# InkTime_SCH.net
KiCad netlist of a schematic drawn in EAGLE
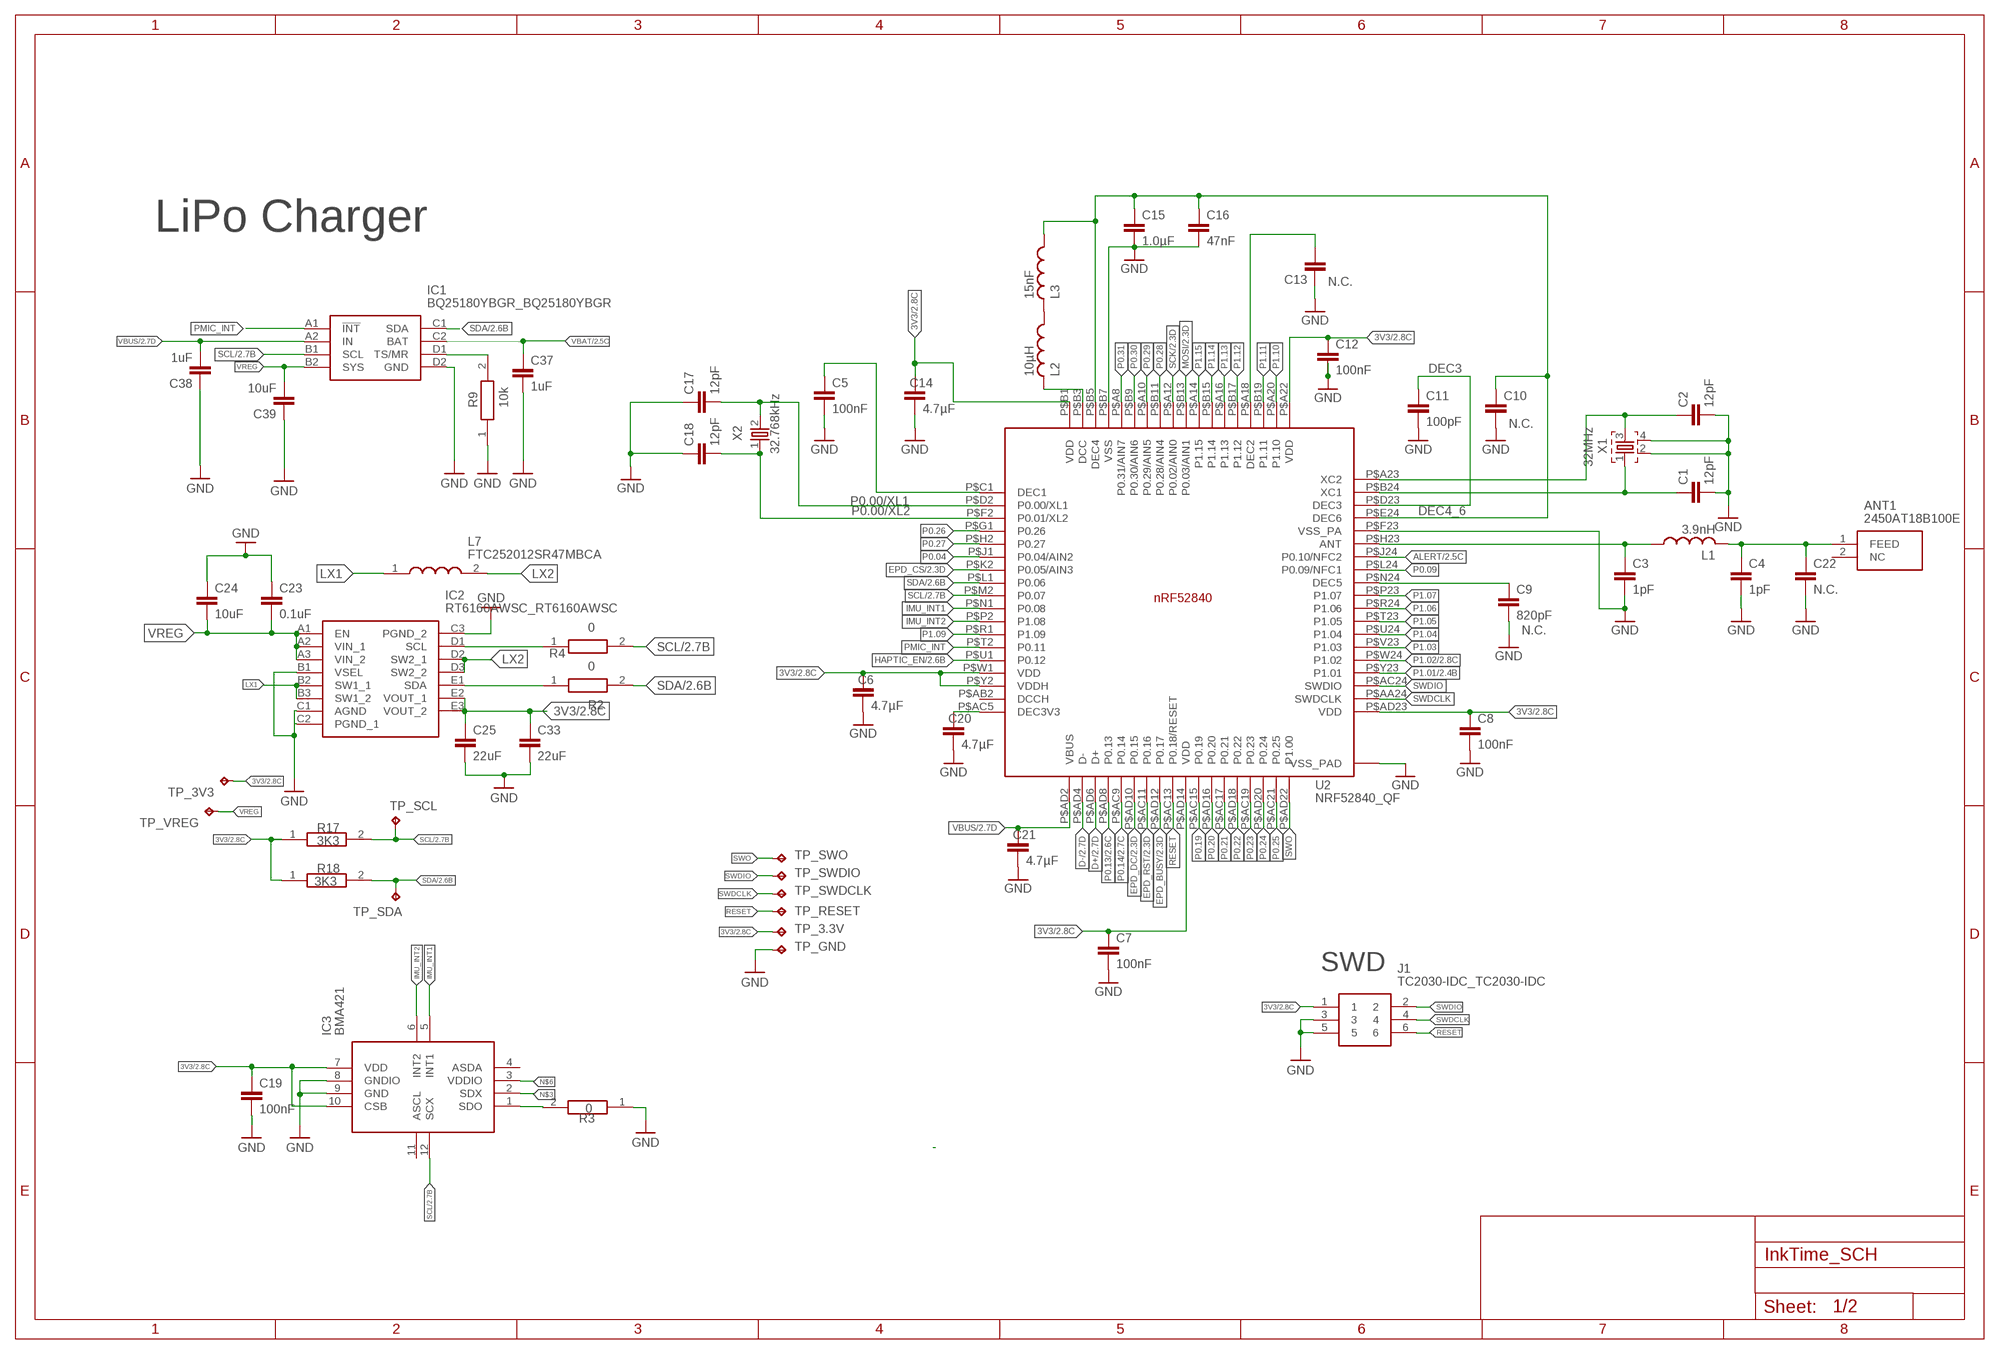
[diagram p0: schematic, sheet 1]
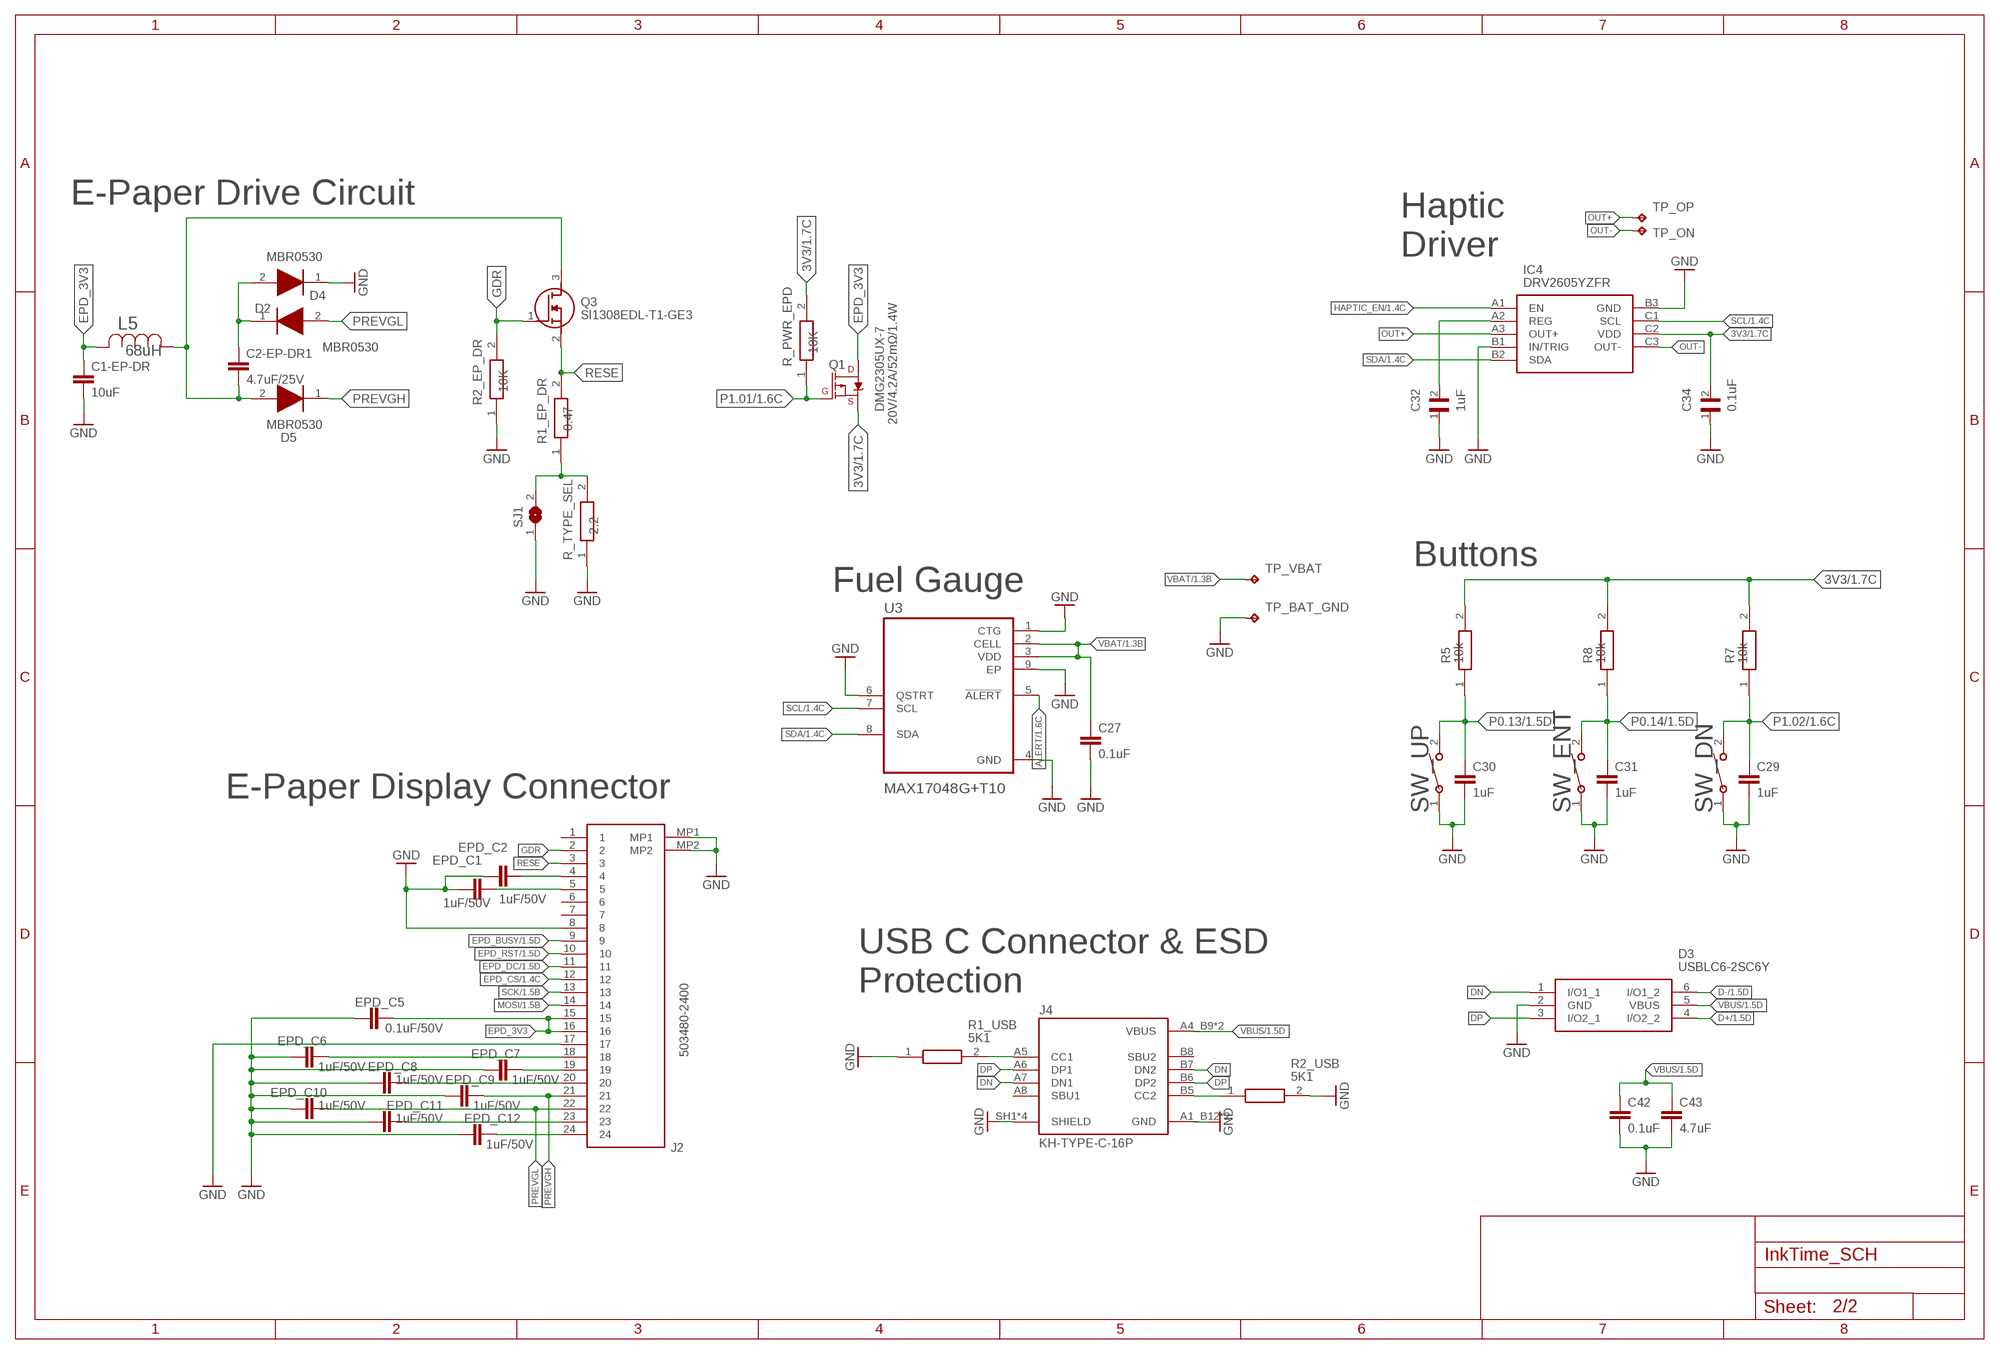
[diagram p1: schematic, sheet 2]

(export (version "E")
  (design (tool "Eeschema 10.0.6"))
  (components
    (comp (ref "ANT1")
      (value "2450AT18B100E")
      (footprint "eagle-import:2450AT18B100E_ANTC3216X140N")
      (fields (field (name "MOUSER_PART_NUMBER") "609-2450AT18B100E"))
      (libsource (lib "eagle-import") (part "2450AT18B100E_2450AT18B100E"))
    )
    (comp (ref "C1")
      (value "12pF")
      (footprint "eagle-import:NORDIC_NRF_3_RESC0201_L")
      (libsource (lib "eagle-import") (part "NORDIC_NRF_3_CAPACITOR_0201_L"))
    )
    (comp (ref "C2")
      (value "12pF")
      (footprint "eagle-import:NORDIC_NRF_3_RESC0201_L")
      (libsource (lib "eagle-import") (part "NORDIC_NRF_3_CAPACITOR_0201_L"))
    )
    (comp (ref "C3")
      (value "1pF")
      (footprint "eagle-import:NORDIC_NRF_3_RESC0201_L")
      (libsource (lib "eagle-import") (part "NORDIC_NRF_3_CAPACITOR_0201_L"))
    )
    (comp (ref "C4")
      (value "1pF")
      (footprint "eagle-import:NORDIC_NRF_3_RESC0201_L")
      (libsource (lib "eagle-import") (part "NORDIC_NRF_3_CAPACITOR_0201_L"))
    )
    (comp (ref "C5")
      (value "100nF")
      (footprint "eagle-import:NORDIC_NRF_3_RESC0201_L")
      (libsource (lib "eagle-import") (part "NORDIC_NRF_3_CAPACITOR_0201_L"))
    )
    (comp (ref "C6")
      (value "4.7µF")
      (footprint "eagle-import:NORDIC_NRF_3_RESC0402_L")
      (libsource (lib "eagle-import") (part "NORDIC_NRF_3_CAPACITOR_0402_L"))
    )
    (comp (ref "C7")
      (value "100nF")
      (footprint "eagle-import:NORDIC_NRF_3_RESC0201_L")
      (libsource (lib "eagle-import") (part "NORDIC_NRF_3_CAPACITOR_0201_L"))
    )
    (comp (ref "C8")
      (value "100nF")
      (footprint "eagle-import:NORDIC_NRF_3_RESC0201_L")
      (libsource (lib "eagle-import") (part "NORDIC_NRF_3_CAPACITOR_0201_L"))
    )
    (comp (ref "C9")
      (value "820pF")
      (footprint "eagle-import:NORDIC_NRF_3_RESC0201_L")
      (libsource (lib "eagle-import") (part "NORDIC_NRF_3_CAPACITOR_0201_L"))
    )
    (comp (ref "C10")
      (value "NORDIC_NRF_3_CAPACITOR_0201_L")
      (footprint "eagle-import:NORDIC_NRF_3_RESC0201_L")
      (libsource (lib "eagle-import") (part "NORDIC_NRF_3_CAPACITOR_0201_L"))
    )
    (comp (ref "C11")
      (value "100pF")
      (footprint "eagle-import:NORDIC_NRF_3_RESC0201_L")
      (libsource (lib "eagle-import") (part "NORDIC_NRF_3_CAPACITOR_0201_L"))
    )
    (comp (ref "C12")
      (value "100nF")
      (footprint "eagle-import:NORDIC_NRF_3_RESC0201_L")
      (libsource (lib "eagle-import") (part "NORDIC_NRF_3_CAPACITOR_0201_L"))
    )
    (comp (ref "C13")
      (value "NORDIC_NRF_3_CAPACITOR_0201_L")
      (footprint "eagle-import:NORDIC_NRF_3_RESC0201_L")
      (libsource (lib "eagle-import") (part "NORDIC_NRF_3_CAPACITOR_0201_L"))
    )
    (comp (ref "C14")
      (value "4.7µF")
      (footprint "eagle-import:NORDIC_NRF_3_RESC0402_L")
      (libsource (lib "eagle-import") (part "NORDIC_NRF_3_CAPACITOR_0402_L"))
    )
    (comp (ref "C15")
      (value "1.0µF")
      (footprint "eagle-import:NORDIC_NRF_3_RESC0402_L")
      (libsource (lib "eagle-import") (part "NORDIC_NRF_3_CAPACITOR_0402_L"))
    )
    (comp (ref "C16")
      (value "47nF")
      (footprint "eagle-import:NORDIC_NRF_3_RESC0201_L")
      (libsource (lib "eagle-import") (part "NORDIC_NRF_3_CAPACITOR_0201_L"))
    )
    (comp (ref "C17")
      (value "12pF")
      (footprint "eagle-import:NORDIC_NRF_3_RESC0201_L")
      (libsource (lib "eagle-import") (part "NORDIC_NRF_3_CAPACITOR_0201_L"))
    )
    (comp (ref "C18")
      (value "12pF")
      (footprint "eagle-import:NORDIC_NRF_3_RESC0201_L")
      (libsource (lib "eagle-import") (part "NORDIC_NRF_3_CAPACITOR_0201_L"))
    )
    (comp (ref "C19")
      (value "100nF")
      (footprint "eagle-import:NORDIC_NRF_3_RESC0201_L")
      (libsource (lib "eagle-import") (part "InkTime_v5_vf.cpZt_fPRRlWDsZKqzDdmXA_NORDIC_NRF_3_CAPACITOR_0201_L"))
    )
    (comp (ref "C20")
      (value "4.7µF")
      (footprint "eagle-import:NORDIC_NRF_3_RESC0402_L")
      (libsource (lib "eagle-import") (part "NORDIC_NRF_3_CAPACITOR_0402_L"))
    )
    (comp (ref "C21")
      (value "4.7µF")
      (footprint "eagle-import:NORDIC_NRF_3_RESC0402_L")
      (libsource (lib "eagle-import") (part "NORDIC_NRF_3_CAPACITOR_0402_L"))
    )
    (comp (ref "C22")
      (value "N.C.")
      (footprint "eagle-import:NORDIC_NRF_3_RESC0201_L")
      (libsource (lib "eagle-import") (part "NORDIC_NRF_3_CAPACITOR_0201_L"))
    )
    (comp (ref "C23")
      (value "0.1uF")
      (footprint "eagle-import:NORDIC_NRF_3_RESC0201_L")
      (libsource (lib "eagle-import") (part "InkTime_v5_vf.cpZt_fPRRlWDsZKqzDdmXA_NORDIC_NRF_3_CAPACITOR_0201_L"))
    )
    (comp (ref "C24")
      (value "10uF")
      (footprint "eagle-import:NORDIC_NRF_3_RESC0402_L")
      (libsource (lib "eagle-import") (part "InkTime_v5_vf.cpZt_fPRRlWDsZKqzDdmXA_NORDIC_NRF_3_CAPACITOR_0402_L"))
    )
    (comp (ref "C25")
      (value "22uF")
      (footprint "eagle-import:NORDIC_NRF_3_RESC0402_L")
      (libsource (lib "eagle-import") (part "InkTime_v5_vf.cpZt_fPRRlWDsZKqzDdmXA_NORDIC_NRF_3_CAPACITOR_0402_L"))
    )
    (comp (ref "C33")
      (value "22uF")
      (footprint "eagle-import:NORDIC_NRF_3_RESC0402_L")
      (libsource (lib "eagle-import") (part "InkTime_v5_vf.cpZt_fPRRlWDsZKqzDdmXA_NORDIC_NRF_3_CAPACITOR_0402_L"))
    )
    (comp (ref "C37")
      (value "1uF")
      (footprint "eagle-import:NORDIC_NRF_3_RESC0402_L")
      (libsource (lib "eagle-import") (part "InkTime_v5_vf.cpZt_fPRRlWDsZKqzDdmXA_NORDIC_NRF_3_CAPACITOR_0402_L"))
    )
    (comp (ref "C38")
      (value "1uF")
      (footprint "eagle-import:NORDIC_NRF_3_RESC0402_L")
      (libsource (lib "eagle-import") (part "InkTime_v5_vf.cpZt_fPRRlWDsZKqzDdmXA_NORDIC_NRF_3_CAPACITOR_0402_L"))
    )
    (comp (ref "C39")
      (value "10uF")
      (footprint "eagle-import:NORDIC_NRF_3_RESC0402_L")
      (libsource (lib "eagle-import") (part "InkTime_v5_vf.cpZt_fPRRlWDsZKqzDdmXA_NORDIC_NRF_3_CAPACITOR_0402_L"))
    )
    (comp (ref "IC1")
      (value "BQ25180YBGR_BQ25180YBGR")
      (footprint "eagle-import:BQ25180YBGR_BGA8C40P2X4_100X155X50")
      (fields
        (field (name "ARROW_PART_NUMBER") "BQ25180YBGR")
        (field (name "MOUSER_PART_NUMBER") "595-BQ25180YBGR")
      )
      (libsource (lib "eagle-import") (part "BQ25180YBGR_BQ25180YBGR"))
    )
    (comp (ref "IC2")
      (value "RT6160AWSC_RT6160AWSC")
      (footprint "eagle-import:RT6160AWSC_BGA15C40P3X5_140X230X60")
      (fields
        (field (name "MANUFACTURER_PART_NUMBER") "RT6160AWSC")
        (field (name "MOUSER_PART_NUMBER") "835-RT6160AWSC")
      )
      (libsource (lib "eagle-import") (part "RT6160AWSC_RT6160AWSC"))
    )
    (comp (ref "IC3")
      (value "BMA421")
      (footprint "eagle-import:BMA423_BMA423")
      (fields (field (name "ARROW_PART_NUMBER") "BMA423") (field (name "MOUSER_PART_NUMBER") "262-BMA423"))
      (libsource (lib "eagle-import") (part "BMA423_BMA423"))
    )
    (comp (ref "J1")
      (value "TC2030-IDC_TC2030-IDC")
      (footprint "eagle-import:TC2030-IDC_TC2030IDC")
      (fields (field (name "MANUFACTURER_PART_NUMBER") "TC2030-IDC"))
      (libsource (lib "eagle-import") (part "TC2030-IDC_TC2030-IDC"))
    )
    (comp (ref "L1")
      (value "3.9nH")
      (footprint "eagle-import:NORDIC_NRF_2_RESC0402_L")
      (libsource (lib "eagle-import") (part "NORDIC_NRF_2_INDUCTOR_0402_L"))
    )
    (comp (ref "L2")
      (value "10µH")
      (footprint "eagle-import:NORDIC_NRF_2_RESC0402_L")
      (libsource (lib "eagle-import") (part "NORDIC_NRF_2_INDUCTOR_0402_L"))
    )
    (comp (ref "L3")
      (value "15nF")
      (footprint "eagle-import:NORDIC_NRF_2_RESC0402_L")
      (libsource (lib "eagle-import") (part "NORDIC_NRF_2_INDUCTOR_0402_L"))
    )
    (comp (ref "L7")
      (value "FTC252012SR47MBCA")
      (footprint "eagle-import:MLP2016SR47MT0S1_INDC2016X100N")
      (libsource (lib "eagle-import") (part "MLP2016SR47MT0S1_FTC252012SR47MBCA"))
    )
    (comp (ref "R2")
      (value "0")
      (footprint "eagle-import:ERA-1AEB3401C_0201")
      (libsource (lib "eagle-import") (part "ERA-1AEB3401C_CPF0201D7K68C1"))
    )
    (comp (ref "R3")
      (value "0")
      (footprint "eagle-import:ERA-1AEB3401C_0201")
      (libsource (lib "eagle-import") (part "ERA-1AEB3401C_CPF0201D7K68C1"))
    )
    (comp (ref "R4")
      (value "0")
      (footprint "eagle-import:ERA-1AEB3401C_0201")
      (libsource (lib "eagle-import") (part "ERA-1AEB3401C_CPF0201D7K68C1"))
    )
    (comp (ref "R9")
      (value "10k")
      (footprint "eagle-import:ERA-1AEB3401C_0201")
      (libsource (lib "eagle-import") (part "ERA-1AEB3401C_CPF0201D7K68C1"))
    )
    (comp (ref "R17")
      (value "3K3")
      (footprint "eagle-import:ERA-1AEB3401C_0201")
      (libsource (lib "eagle-import") (part "ERA-1AEB3401C_CPF0201D7K68C1"))
    )
    (comp (ref "R18")
      (value "3K3")
      (footprint "eagle-import:ERA-1AEB3401C_0201")
      (libsource (lib "eagle-import") (part "ERA-1AEB3401C_CPF0201D7K68C1"))
    )
    (comp (ref "TP_3.3V")
      (value "HECTOR_WATCH_1_TPTP20R")
      (footprint "eagle-import:HECTOR_WATCH_1_TP20R")
      (libsource (lib "eagle-import") (part "InkTime_v5_vf.cpZt_fPRRlWDsZKqzDdmXA_HECTOR_WATCH_1_TPTP20R"))
    )
    (comp (ref "TP_3V3")
      (value "HECTOR_WATCH_1_TPTP20R")
      (footprint "eagle-import:HECTOR_WATCH_1_TP20R")
      (libsource (lib "eagle-import") (part "InkTime_v5_vf.cpZt_fPRRlWDsZKqzDdmXA_HECTOR_WATCH_1_TPTP20R"))
    )
    (comp (ref "TP_GND")
      (value "HECTOR_WATCH_1_TPTP20R")
      (footprint "eagle-import:HECTOR_WATCH_1_TP20R")
      (libsource (lib "eagle-import") (part "InkTime_v5_vf.cpZt_fPRRlWDsZKqzDdmXA_HECTOR_WATCH_1_TPTP20R"))
    )
    (comp (ref "TP_RESET")
      (value "HECTOR_WATCH_1_TPTP20R")
      (footprint "eagle-import:HECTOR_WATCH_1_TP20R")
      (libsource (lib "eagle-import") (part "InkTime_v5_vf.cpZt_fPRRlWDsZKqzDdmXA_HECTOR_WATCH_1_TPTP20R"))
    )
    (comp (ref "TP_SCL")
      (value "HECTOR_WATCH_1_TPTP20R")
      (footprint "eagle-import:HECTOR_WATCH_1_TP20R")
      (libsource (lib "eagle-import") (part "InkTime_v5_vf.cpZt_fPRRlWDsZKqzDdmXA_HECTOR_WATCH_1_TPTP20R"))
    )
    (comp (ref "TP_SDA")
      (value "HECTOR_WATCH_1_TPTP20R")
      (footprint "eagle-import:HECTOR_WATCH_1_TP20R")
      (libsource (lib "eagle-import") (part "InkTime_v5_vf.cpZt_fPRRlWDsZKqzDdmXA_HECTOR_WATCH_1_TPTP20R"))
    )
    (comp (ref "TP_SWDCLK")
      (value "HECTOR_WATCH_1_TPTP20R")
      (footprint "eagle-import:HECTOR_WATCH_1_TP20R")
      (libsource (lib "eagle-import") (part "InkTime_v5_vf.cpZt_fPRRlWDsZKqzDdmXA_HECTOR_WATCH_1_TPTP20R"))
    )
    (comp (ref "TP_SWDIO")
      (value "HECTOR_WATCH_1_TPTP20R")
      (footprint "eagle-import:HECTOR_WATCH_1_TP20R")
      (libsource (lib "eagle-import") (part "InkTime_v5_vf.cpZt_fPRRlWDsZKqzDdmXA_HECTOR_WATCH_1_TPTP20R"))
    )
    (comp (ref "TP_SWO")
      (value "HECTOR_WATCH_1_TPTP20R")
      (footprint "eagle-import:HECTOR_WATCH_1_TP20R")
      (libsource (lib "eagle-import") (part "InkTime_v5_vf.cpZt_fPRRlWDsZKqzDdmXA_HECTOR_WATCH_1_TPTP20R"))
    )
    (comp (ref "TP_VREG")
      (value "HECTOR_WATCH_1_TPTP20R")
      (footprint "eagle-import:HECTOR_WATCH_1_TP20R")
      (libsource (lib "eagle-import") (part "InkTime_v5_vf.cpZt_fPRRlWDsZKqzDdmXA_HECTOR_WATCH_1_TPTP20R"))
    )
    (comp (ref "U2")
      (value "NRF52840_QF")
      (footprint "eagle-import:NORDIC_NRF_4_AQFN50P700X700X85_HS-74N")
      (libsource (lib "eagle-import") (part "NORDIC_NRF_4_NRF52840_QF"))
    )
    (comp (ref "X1")
      (value "32MHz")
      (footprint "eagle-import:NORDIC_NRF_BT-XTAL_2016_N")
      (libsource (lib "eagle-import") (part "NORDIC_NRF_XTAL_32MHZ"))
    )
    (comp (ref "X2")
      (value "32.768kHz")
      (footprint "eagle-import:NORDIC_NRF_1_XTAL_3215_N")
      (libsource (lib "eagle-import") (part "NORDIC_NRF_1_XTAL_32KHZ"))
    )
    (comp (ref "C1-EP-DR")
      (value "10uF")
      (footprint "eagle-import:NORDIC_NRF_3_RESC0402_L")
      (libsource (lib "eagle-import") (part "NORDIC_NRF_3_CAPACITOR_0402_L"))
    )
    (comp (ref "C2-EP-DR1")
      (value "4.7uF/25V")
      (footprint "eagle-import:NORDIC_NRF_3_RESC0402_L")
      (libsource (lib "eagle-import") (part "NORDIC_NRF_3_CAPACITOR_0402_L"))
    )
    (comp (ref "C27")
      (value "0.1uF")
      (footprint "eagle-import:NORDIC_NRF_3_RESC0201_L")
      (libsource (lib "eagle-import") (part "NORDIC_NRF_3_CAPACITOR_0201_L"))
    )
    (comp (ref "C29")
      (value "1uF")
      (footprint "eagle-import:NORDIC_NRF_3_RESC0402_L")
      (libsource (lib "eagle-import") (part "NORDIC_NRF_3_CAPACITOR_0402_L"))
    )
    (comp (ref "C30")
      (value "1uF")
      (footprint "eagle-import:NORDIC_NRF_3_RESC0402_L")
      (libsource (lib "eagle-import") (part "NORDIC_NRF_3_CAPACITOR_0402_L"))
    )
    (comp (ref "C31")
      (value "1uF")
      (footprint "eagle-import:NORDIC_NRF_3_RESC0402_L")
      (libsource (lib "eagle-import") (part "NORDIC_NRF_3_CAPACITOR_0402_L"))
    )
    (comp (ref "C32")
      (value "1uF")
      (footprint "eagle-import:GRM011R60J152KE01L_2_CAPC0201X13N")
      (fields (field (name "MF") "Murata") (field (name "MP") "GRM011R60J152KE01L"))
      (libsource (lib "eagle-import") (part "GRM011R60J152KE01L_2_GRM011R60J152KE01L"))
    )
    (comp (ref "C34")
      (value "0.1uF")
      (footprint "eagle-import:GRM011R60J152KE01L_2_CAPC0201X13N")
      (fields (field (name "MF") "Murata") (field (name "MP") "GRM011R60J152KE01L"))
      (libsource (lib "eagle-import") (part "GRM011R60J152KE01L_2_GRM011R60J152KE01L"))
    )
    (comp (ref "C42")
      (value "0.1uF")
      (footprint "eagle-import:NORDIC_NRF_3_RESC0201_L")
      (libsource (lib "eagle-import") (part "NORDIC_NRF_3_CAPACITOR_0201_L"))
    )
    (comp (ref "C43")
      (value "4.7uF")
      (footprint "eagle-import:NORDIC_NRF_3_RESC0402_L")
      (libsource (lib "eagle-import") (part "NORDIC_NRF_3_CAPACITOR_0402_L"))
    )
    (comp (ref "D2")
      (value "MBR0530")
      (footprint "eagle-import:ESP32_C6_LIBRARY_5_SOD3716X135N")
      (fields (field (name "MF") "ON Semiconductor"))
      (libsource (lib "eagle-import") (part "ESP32_C6_LIBRARY_5_MBR0530"))
    )
    (comp (ref "D3")
      (value "USBLC6-2SC6Y")
      (footprint "eagle-import:ESP32_C6_LIBRARY_3_SOT95P280X145-6N")
      (fields (field (name "MF") "STMicroelectronics"))
      (libsource (lib "eagle-import") (part "ESP32_C6_LIBRARY_3_USBLC6-2SC6Y"))
    )
    (comp (ref "D4")
      (value "MBR0530")
      (footprint "eagle-import:ESP32_C6_LIBRARY_5_SOD3716X135N")
      (fields (field (name "MF") "ON Semiconductor"))
      (libsource (lib "eagle-import") (part "ESP32_C6_LIBRARY_5_MBR0530"))
    )
    (comp (ref "D5")
      (value "MBR0530")
      (footprint "eagle-import:ESP32_C6_LIBRARY_5_SOD3716X135N")
      (fields (field (name "MF") "ON Semiconductor"))
      (libsource (lib "eagle-import") (part "ESP32_C6_LIBRARY_5_MBR0530"))
    )
    (comp (ref "EPD_C1")
      (value "1uF/50V")
      (footprint "eagle-import:NORDIC_NRF_3_RESC0402_L")
      (libsource (lib "eagle-import") (part "NORDIC_NRF_3_CAPACITOR_0402_L"))
    )
    (comp (ref "EPD_C2")
      (value "1uF/50V")
      (footprint "eagle-import:NORDIC_NRF_3_RESC0402_L")
      (libsource (lib "eagle-import") (part "NORDIC_NRF_3_CAPACITOR_0402_L"))
    )
    (comp (ref "EPD_C5")
      (value "0.1uF/50V")
      (footprint "eagle-import:NORDIC_NRF_3_RESC0201_L")
      (libsource (lib "eagle-import") (part "NORDIC_NRF_3_CAPACITOR_0201_L"))
    )
    (comp (ref "EPD_C6")
      (value "1uF/50V")
      (footprint "eagle-import:NORDIC_NRF_3_RESC0402_L")
      (libsource (lib "eagle-import") (part "NORDIC_NRF_3_CAPACITOR_0402_L"))
    )
    (comp (ref "EPD_C7")
      (value "1uF/50V")
      (footprint "eagle-import:NORDIC_NRF_3_RESC0402_L")
      (libsource (lib "eagle-import") (part "NORDIC_NRF_3_CAPACITOR_0402_L"))
    )
    (comp (ref "EPD_C8")
      (value "1uF/50V")
      (footprint "eagle-import:NORDIC_NRF_3_RESC0402_L")
      (libsource (lib "eagle-import") (part "NORDIC_NRF_3_CAPACITOR_0402_L"))
    )
    (comp (ref "EPD_C9")
      (value "1uF/50V")
      (footprint "eagle-import:NORDIC_NRF_3_RESC0402_L")
      (libsource (lib "eagle-import") (part "NORDIC_NRF_3_CAPACITOR_0402_L"))
    )
    (comp (ref "EPD_C10")
      (value "1uF/50V")
      (footprint "eagle-import:NORDIC_NRF_3_RESC0402_L")
      (libsource (lib "eagle-import") (part "NORDIC_NRF_3_CAPACITOR_0402_L"))
    )
    (comp (ref "EPD_C11")
      (value "1uF/50V")
      (footprint "eagle-import:NORDIC_NRF_3_RESC0402_L")
      (libsource (lib "eagle-import") (part "NORDIC_NRF_3_CAPACITOR_0402_L"))
    )
    (comp (ref "EPD_C12")
      (value "1uF/50V")
      (footprint "eagle-import:NORDIC_NRF_3_RESC0402_L")
      (libsource (lib "eagle-import") (part "NORDIC_NRF_3_CAPACITOR_0402_L"))
    )
    (comp (ref "IC4")
      (value "DRV2605YZFR")
      (footprint "eagle-import:DRV2605YZFR_BGA9C50P3X3_144X144X62")
      (libsource (lib "eagle-import") (part "DRV2605YZFR_DRV2605YZFR"))
    )
    (comp (ref "J2")
      (value "503480-2400")
      (footprint "eagle-import:503480-2400_5034802400")
      (fields (field (name "MOUSER_PART_NUMBER") "538-503480-2400"))
      (libsource (lib "eagle-import") (part "503480-2400_503480-2400"))
    )
    (comp (ref "J4")
      (value "KH-TYPE-C-16P")
      (footprint "eagle-import:KH-TYPE-C-16P_KINGHELM_KH-TYPE-C-16P")
      (fields (field (name "MF") "kinghelm"))
      (libsource (lib "eagle-import") (part "KH-TYPE-C-16P_KH-TYPE-C-16P"))
    )
    (comp (ref "L5")
      (value "68uH")
      (footprint "eagle-import:ESP32_C6_LIBRARY_2_IND_4828-WE-TPC_WRE")
      (fields
        (field (name "MANUFACTURER_PART_NUMBER") "744043680")
        (field (name "COPYRIGHT") "Copyright (C) 2024 Ultra Librarian. All rights reserved.")
      )
      (libsource (lib "eagle-import") (part "ESP32_C6_LIBRARY_2_744043680IND_4828-WE-TPC_WRE"))
    )
    (comp (ref "Q1")
      (value "20V/4.2A/52mΩ/1.4W")
      (footprint "eagle-import:ESP32_C6_LIBRARY_4_ESP32_C6_LIBRARY_4_ESP32_C6_LIBRARY_4_ESP32_C6_LIBRARY_4_ESP32_WROVER_SPARKFUN-DISCRETESEMI_SOT23-3")
      (libsource (lib "eagle-import") (part "ESP32_C6_LIBRARY_4_ESP32_WROVER_SPARKFUN-DISCRETESEMI_MOSFET_PCH-DMG2305UX-7"))
    )
    (comp (ref "Q3")
      (value "SI1308EDL-T1-GE3")
      (footprint "eagle-import:ESP32_C6_LIBRARY_6_SOT65P210X110-3N")
      (fields (field (name "MF") "Vishay Siliconix"))
      (libsource (lib "eagle-import") (part "ESP32_C6_LIBRARY_6_SI1308EDL-T1-GE3"))
    )
    (comp (ref "R1_EP_DR")
      (value "0.47")
      (footprint "eagle-import:CPF0201D7K68C1_0201")
      (libsource (lib "eagle-import") (part "CPF0201D7K68C1_CPF0201D7K68C1"))
    )
    (comp (ref "R1_USB")
      (value "5K1")
      (footprint "eagle-import:ERA-1AEB3401C_0201")
      (libsource (lib "eagle-import") (part "InkTime_v5_vf.fkz7WSyWSr61TWkXU9X4_w_ERA-1AEB3401C_CPF0201D7K68C1"))
    )
    (comp (ref "R2_EP_DR")
      (value "10K")
      (footprint "eagle-import:CPF0201D7K68C1_0201")
      (libsource (lib "eagle-import") (part "CPF0201D7K68C1_CPF0201D7K68C1"))
    )
    (comp (ref "R2_USB")
      (value "5K1")
      (footprint "eagle-import:ERA-1AEB3401C_0201")
      (libsource (lib "eagle-import") (part "InkTime_v5_vf.fkz7WSyWSr61TWkXU9X4_w_ERA-1AEB3401C_CPF0201D7K68C1"))
    )
    (comp (ref "R5")
      (value "10k")
      (footprint "eagle-import:CPF0201D7K68C1_0201")
      (libsource (lib "eagle-import") (part "CPF0201D7K68C1_CPF0201D7K68C1"))
    )
    (comp (ref "R7")
      (value "10k")
      (footprint "eagle-import:CPF0201D7K68C1_0201")
      (libsource (lib "eagle-import") (part "CPF0201D7K68C1_CPF0201D7K68C1"))
    )
    (comp (ref "R8")
      (value "10k")
      (footprint "eagle-import:CPF0201D7K68C1_0201")
      (libsource (lib "eagle-import") (part "CPF0201D7K68C1_CPF0201D7K68C1"))
    )
    (comp (ref "R_PWR_EPD")
      (value "10K")
      (footprint "eagle-import:CPF0201D7K68C1_0201")
      (libsource (lib "eagle-import") (part "CPF0201D7K68C1_CPF0201D7K68C1"))
    )
    (comp (ref "R_TYPE_SEL")
      (value "2.2")
      (footprint "eagle-import:CPF0201D7K68C1_0201")
      (libsource (lib "eagle-import") (part "CPF0201D7K68C1_CPF0201D7K68C1"))
    )
    (comp (ref "SJ1")
      (value "ESP32_C6_LIBRARY_7_JUMPER_SJ")
      (footprint "eagle-import:ESP32_C6_LIBRARY_7_JUMPER_SJ")
      (libsource (lib "eagle-import") (part "ESP32_C6_LIBRARY_7_JUMPER_SJ"))
    )
    (comp (ref "SW_DN")
      (value "2025-10-22_07-23-44_LIBRARY_EVP-AKE31ASW_EVP-AKE31A_PAN")
      (footprint "eagle-import:2025-10-22_07-23-44_LIBRARY_SW_EVP-AKE31A_PAN")
      (fields
        (field (name "MANUFACTURER_PART_NUMBER") "EVP-AKE31A")
        (field (name "COPYRIGHT") "Copyright (C) 2025 Ultra Librarian. All rights reserved.")
      )
      (libsource (lib "eagle-import") (part "2025-10-22_07-23-44_LIBRARY_EVP-AKE31ASW_EVP-AKE31A_PAN"))
    )
    (comp (ref "SW_ENT")
      (value "SW_ENT")
      (footprint "eagle-import:2025-10-22_07-23-44_LIBRARY_SW_EVP-AKE31A_PAN")
      (fields
        (field (name "MANUFACTURER_PART_NUMBER") "EVP-AKE31A")
        (field (name "COPYRIGHT") "Copyright (C) 2025 Ultra Librarian. All rights reserved.")
      )
      (libsource (lib "eagle-import") (part "2025-10-22_07-23-44_LIBRARY_EVP-AKE31ASW_EVP-AKE31A_PAN"))
    )
    (comp (ref "SW_UP")
      (value "2025-10-22_07-23-44_LIBRARY_EVP-AKE31ASW_EVP-AKE31A_PAN")
      (footprint "eagle-import:2025-10-22_07-23-44_LIBRARY_SW_EVP-AKE31A_PAN")
      (fields
        (field (name "MANUFACTURER_PART_NUMBER") "EVP-AKE31A")
        (field (name "COPYRIGHT") "Copyright (C) 2025 Ultra Librarian. All rights reserved.")
      )
      (libsource (lib "eagle-import") (part "2025-10-22_07-23-44_LIBRARY_EVP-AKE31ASW_EVP-AKE31A_PAN"))
    )
    (comp (ref "TP_BAT_GND")
      (value "HECTOR_WATCH_1_TPTP20R")
      (footprint "eagle-import:HECTOR_WATCH_1_TP20R")
      (libsource (lib "eagle-import") (part "HECTOR_WATCH_1_TPTP20R"))
    )
    (comp (ref "TP_ON")
      (value "HECTOR_WATCH_1_TPTP20R")
      (footprint "eagle-import:HECTOR_WATCH_1_TP20R")
      (libsource (lib "eagle-import") (part "HECTOR_WATCH_1_TPTP20R"))
    )
    (comp (ref "TP_OP")
      (value "HECTOR_WATCH_1_TPTP20R")
      (footprint "eagle-import:HECTOR_WATCH_1_TP20R")
      (libsource (lib "eagle-import") (part "HECTOR_WATCH_1_TPTP20R"))
    )
    (comp (ref "TP_VBAT")
      (value "HECTOR_WATCH_1_TPTP20R")
      (footprint "eagle-import:HECTOR_WATCH_1_TP20R")
      (libsource (lib "eagle-import") (part "HECTOR_WATCH_1_TPTP20R"))
    )
    (comp (ref "U3")
      (value "MAX17048G+T10")
      (footprint "eagle-import:ESP32_C6_LIBRARY_SON50P200X200X80-9N")
      (fields (field (name "MF") "Analog Devices"))
      (libsource (lib "eagle-import") (part "ESP32_C6_LIBRARY_MAX17048G+T10"))
    )
  )
  (nets
    (net (code "1") (name "3V3") (class "Default")
      (node (ref "C12") (pin "1") (pinfunction "1_1") (pintype "passive"))
      (node (ref "C14") (pin "1") (pinfunction "1_1") (pintype "passive"))
      (node (ref "C19") (pin "1") (pinfunction "1_1") (pintype "passive"))
      (node (ref "C25") (pin "1") (pinfunction "1_1") (pintype "passive"))
      (node (ref "C33") (pin "1") (pinfunction "1_1") (pintype "passive"))
      (node (ref "C34") (pin "2") (pinfunction "2_2") (pintype "passive"))
      (node (ref "C6") (pin "1") (pinfunction "1_1") (pintype "passive"))
      (node (ref "C7") (pin "1") (pinfunction "1_1") (pintype "passive"))
      (node (ref "C8") (pin "1") (pinfunction "1_1") (pintype "passive"))
      (node (ref "IC2") (pin "E2") (pinfunction "VOUT_1_E2") (pintype "bidirectional"))
      (node (ref "IC2") (pin "E3") (pinfunction "VOUT_2_E3") (pintype "bidirectional"))
      (node (ref "IC3") (pin "10") (pinfunction "CSB_10") (pintype "bidirectional"))
      (node (ref "IC3") (pin "7") (pinfunction "VDD_7") (pintype "bidirectional"))
      (node (ref "IC4") (pin "C2") (pinfunction "VDD_C2") (pintype "bidirectional"))
      (node (ref "J1") (pin "1") (pinfunction "1_1") (pintype "bidirectional"))
      (node (ref "Q1") (pin "2") (pinfunction "S_2") (pintype "bidirectional"))
      (node (ref "R17") (pin "1") (pinfunction "1_1") (pintype "bidirectional"))
      (node (ref "R18") (pin "1") (pinfunction "1_1") (pintype "bidirectional"))
      (node (ref "R5") (pin "2") (pinfunction "2_2") (pintype "bidirectional"))
      (node (ref "R7") (pin "2") (pinfunction "2_2") (pintype "bidirectional"))
      (node (ref "R8") (pin "2") (pinfunction "2_2") (pintype "bidirectional"))
      (node (ref "R_PWR_EPD") (pin "2") (pinfunction "2_2") (pintype "bidirectional"))
      (node (ref "TP_3.3V") (pin "TP") (pinfunction "TP_TP") (pintype "input"))
      (node (ref "TP_3V3") (pin "TP") (pinfunction "TP_TP") (pintype "input"))
      (node (ref "U2") (pin "P$A22") (pinfunction "VDD_P$A22") (pintype "power_in"))
      (node (ref "U2") (pin "P$AD14") (pinfunction "VDD_P$AD14") (pintype "power_in"))
      (node (ref "U2") (pin "P$AD23") (pinfunction "VDD_P$AD23") (pintype "power_in"))
      (node (ref "U2") (pin "P$B1") (pinfunction "VDD_P$B1") (pintype "power_in"))
      (node (ref "U2") (pin "P$W1") (pinfunction "VDD_P$W1") (pintype "power_in"))
      (node (ref "U2") (pin "P$Y2") (pinfunction "VDDH_P$Y2") (pintype "power_in"))
    )
    (net (code "2") (name "ALERT") (class "Default")
      (node (ref "U2") (pin "P$J24") (pinfunction "P0.10/NFC2_P$J24") (pintype "bidirectional"))
      (node (ref "U3") (pin "5") (pinfunction "~{ALERT}_5") (pintype "output"))
    )
    (net (code "3") (name "D+") (class "Default")
      (node (ref "D3") (pin "4") (pinfunction "I/O2_2_4") (pintype "bidirectional"))
      (node (ref "U2") (pin "P$AD6") (pinfunction "D+_P$AD6") (pintype "bidirectional"))
    )
    (net (code "4") (name "D-") (class "Default")
      (node (ref "D3") (pin "6") (pinfunction "I/O1_2_6") (pintype "bidirectional"))
      (node (ref "U2") (pin "P$AD4") (pinfunction "D-_P$AD4") (pintype "bidirectional"))
    )
    (net (code "5") (name "DEC3") (class "Default")
      (node (ref "C11") (pin "1") (pinfunction "1_1") (pintype "passive"))
      (node (ref "U2") (pin "P$D23") (pinfunction "DEC3_P$D23") (pintype "bidirectional"))
    )
    (net (code "6") (name "DEC4_6") (class "Default")
      (node (ref "C10") (pin "2") (pinfunction "2_2") (pintype "passive"))
      (node (ref "C15") (pin "1") (pinfunction "1_1") (pintype "passive"))
      (node (ref "C16") (pin "1") (pinfunction "1_1") (pintype "passive"))
      (node (ref "L3") (pin "1") (pinfunction "1_1") (pintype "passive"))
      (node (ref "U2") (pin "P$B5") (pinfunction "DEC4_P$B5") (pintype "power_in"))
      (node (ref "U2") (pin "P$E24") (pinfunction "DEC6_P$E24") (pintype "bidirectional"))
    )
    (net (code "7") (name "DN") (class "Default")
      (node (ref "D3") (pin "1") (pinfunction "I/O1_1_1") (pintype "bidirectional"))
      (node (ref "J4") (pin "A7") (pinfunction "DN1_A7") (pintype "bidirectional"))
      (node (ref "J4") (pin "B7") (pinfunction "DN2_B7") (pintype "bidirectional"))
    )
    (net (code "8") (name "DP") (class "Default")
      (node (ref "D3") (pin "3") (pinfunction "I/O2_1_3") (pintype "bidirectional"))
      (node (ref "J4") (pin "A6") (pinfunction "DP1_A6") (pintype "bidirectional"))
      (node (ref "J4") (pin "B6") (pinfunction "DP2_B6") (pintype "bidirectional"))
    )
    (net (code "9") (name "EPD_3V3") (class "Default")
      (node (ref "C1-EP-DR") (pin "1") (pinfunction "1_1") (pintype "passive"))
      (node (ref "EPD_C5") (pin "2") (pinfunction "2_2") (pintype "passive"))
      (node (ref "J2") (pin "15") (pinfunction "15_15") (pintype "bidirectional"))
      (node (ref "J2") (pin "16") (pinfunction "16_16") (pintype "bidirectional"))
      (node (ref "L5") (pin "2") (pinfunction "2_2") (pintype "passive"))
      (node (ref "Q1") (pin "3") (pinfunction "D_3") (pintype "bidirectional"))
    )
    (net (code "10") (name "EPD_BUSY") (class "Default")
      (node (ref "J2") (pin "9") (pinfunction "9_9") (pintype "bidirectional"))
      (node (ref "U2") (pin "P$AD12") (pinfunction "P0.17_P$AD12") (pintype "bidirectional"))
    )
    (net (code "11") (name "EPD_CS") (class "Default")
      (node (ref "J2") (pin "12") (pinfunction "12_12") (pintype "bidirectional"))
      (node (ref "U2") (pin "P$K2") (pinfunction "P0.05/AIN3_P$K2") (pintype "bidirectional"))
    )
    (net (code "12") (name "EPD_DC") (class "Default")
      (node (ref "J2") (pin "11") (pinfunction "11_11") (pintype "bidirectional"))
      (node (ref "U2") (pin "P$AD10") (pinfunction "P0.15_P$AD10") (pintype "bidirectional"))
    )
    (net (code "13") (name "EPD_RST") (class "Default")
      (node (ref "J2") (pin "10") (pinfunction "10_10") (pintype "bidirectional"))
      (node (ref "U2") (pin "P$AC11") (pinfunction "P0.16_P$AC11") (pintype "bidirectional"))
    )
    (net (code "14") (name "GDR") (class "Default")
      (node (ref "J2") (pin "2") (pinfunction "2_2") (pintype "bidirectional"))
      (node (ref "Q3") (pin "1") (pinfunction "G_1") (pintype "bidirectional"))
      (node (ref "R2_EP_DR") (pin "2") (pinfunction "2_2") (pintype "bidirectional"))
    )
    (net (code "15") (name "GND") (class "Default")
      (node (ref "C1") (pin "2") (pinfunction "2_2") (pintype "passive"))
      (node (ref "C1-EP-DR") (pin "2") (pinfunction "2_2") (pintype "passive"))
      (node (ref "C10") (pin "1") (pinfunction "1_1") (pintype "passive"))
      (node (ref "C11") (pin "2") (pinfunction "2_2") (pintype "passive"))
      (node (ref "C12") (pin "2") (pinfunction "2_2") (pintype "passive"))
      (node (ref "C13") (pin "1") (pinfunction "1_1") (pintype "passive"))
      (node (ref "C14") (pin "2") (pinfunction "2_2") (pintype "passive"))
      (node (ref "C15") (pin "2") (pinfunction "2_2") (pintype "passive"))
      (node (ref "C16") (pin "2") (pinfunction "2_2") (pintype "passive"))
      (node (ref "C17") (pin "1") (pinfunction "1_1") (pintype "passive"))
      (node (ref "C18") (pin "1") (pinfunction "1_1") (pintype "passive"))
      (node (ref "C19") (pin "2") (pinfunction "2_2") (pintype "passive"))
      (node (ref "C2") (pin "2") (pinfunction "2_2") (pintype "passive"))
      (node (ref "C20") (pin "2") (pinfunction "2_2") (pintype "passive"))
      (node (ref "C21") (pin "2") (pinfunction "2_2") (pintype "passive"))
      (node (ref "C22") (pin "2") (pinfunction "2_2") (pintype "passive"))
      (node (ref "C23") (pin "1") (pinfunction "1_1") (pintype "passive"))
      (node (ref "C24") (pin "1") (pinfunction "1_1") (pintype "passive"))
      (node (ref "C25") (pin "2") (pinfunction "2_2") (pintype "passive"))
      (node (ref "C27") (pin "2") (pinfunction "2_2") (pintype "passive"))
      (node (ref "C29") (pin "2") (pinfunction "2_2") (pintype "passive"))
      (node (ref "C3") (pin "2") (pinfunction "2_2") (pintype "passive"))
      (node (ref "C30") (pin "2") (pinfunction "2_2") (pintype "passive"))
      (node (ref "C31") (pin "2") (pinfunction "2_2") (pintype "passive"))
      (node (ref "C32") (pin "1") (pinfunction "1_1") (pintype "passive"))
      (node (ref "C33") (pin "2") (pinfunction "2_2") (pintype "passive"))
      (node (ref "C34") (pin "1") (pinfunction "1_1") (pintype "passive"))
      (node (ref "C37") (pin "2") (pinfunction "2_2") (pintype "passive"))
      (node (ref "C38") (pin "1") (pinfunction "1_1") (pintype "passive"))
      (node (ref "C39") (pin "1") (pinfunction "1_1") (pintype "passive"))
      (node (ref "C4") (pin "2") (pinfunction "2_2") (pintype "passive"))
      (node (ref "C42") (pin "2") (pinfunction "2_2") (pintype "passive"))
      (node (ref "C43") (pin "2") (pinfunction "2_2") (pintype "passive"))
      (node (ref "C5") (pin "2") (pinfunction "2_2") (pintype "passive"))
      (node (ref "C6") (pin "2") (pinfunction "2_2") (pintype "passive"))
      (node (ref "C7") (pin "2") (pinfunction "2_2") (pintype "passive"))
      (node (ref "C8") (pin "2") (pinfunction "2_2") (pintype "passive"))
      (node (ref "C9") (pin "2") (pinfunction "2_2") (pintype "passive"))
      (node (ref "D2") (pin "1") (pinfunction "K_1") (pintype "bidirectional"))
      (node (ref "D3") (pin "2") (pinfunction "GND_2") (pintype "bidirectional"))
      (node (ref "EPD_C1") (pin "1") (pinfunction "1_1") (pintype "passive"))
      (node (ref "EPD_C10") (pin "1") (pinfunction "1_1") (pintype "passive"))
      (node (ref "EPD_C11") (pin "1") (pinfunction "1_1") (pintype "passive"))
      (node (ref "EPD_C12") (pin "1") (pinfunction "1_1") (pintype "passive"))
      (node (ref "EPD_C2") (pin "1") (pinfunction "1_1") (pintype "passive"))
      (node (ref "EPD_C5") (pin "1") (pinfunction "1_1") (pintype "passive"))
      (node (ref "EPD_C6") (pin "1") (pinfunction "1_1") (pintype "passive"))
      (node (ref "EPD_C7") (pin "1") (pinfunction "1_1") (pintype "passive"))
      (node (ref "EPD_C8") (pin "1") (pinfunction "1_1") (pintype "passive"))
      (node (ref "EPD_C9") (pin "1") (pinfunction "1_1") (pintype "passive"))
      (node (ref "IC1") (pin "D2") (pinfunction "GND_D2") (pintype "bidirectional"))
      (node (ref "IC2") (pin "B1") (pinfunction "VSEL_B1") (pintype "bidirectional"))
      (node (ref "IC2") (pin "C1") (pinfunction "AGND_C1") (pintype "bidirectional"))
      (node (ref "IC2") (pin "C2") (pinfunction "PGND_1_C2") (pintype "bidirectional"))
      (node (ref "IC2") (pin "C3") (pinfunction "PGND_2_C3") (pintype "bidirectional"))
      (node (ref "IC3") (pin "8") (pinfunction "GNDIO_8") (pintype "bidirectional"))
      (node (ref "IC3") (pin "9") (pinfunction "GND_9") (pintype "bidirectional"))
      (node (ref "IC4") (pin "B1") (pinfunction "IN/TRIG_B1") (pintype "bidirectional"))
      (node (ref "IC4") (pin "B3") (pinfunction "GND_B3") (pintype "bidirectional"))
      (node (ref "J1") (pin "3") (pinfunction "3_3") (pintype "bidirectional"))
      (node (ref "J1") (pin "5") (pinfunction "5_5") (pintype "bidirectional"))
      (node (ref "J2") (pin "17") (pinfunction "17_17") (pintype "bidirectional"))
      (node (ref "J2") (pin "8") (pinfunction "8_8") (pintype "bidirectional"))
      (node (ref "J2") (pin "MP1") (pinfunction "MP1_MP1") (pintype "bidirectional"))
      (node (ref "J2") (pin "MP2") (pinfunction "MP2_MP2") (pintype "bidirectional"))
      (node (ref "J4") (pin "A12_B1") (pinfunction "GND_A12_B1") (pintype "power_in"))
      (node (ref "J4") (pin "A1_B12") (pinfunction "GND_A1_B12") (pintype "power_in"))
      (node (ref "J4") (pin "SH1") (pinfunction "SHIELD_SH1") (pintype "passive"))
      (node (ref "J4") (pin "SH2") (pinfunction "SHIELD_SH2") (pintype "passive"))
      (node (ref "J4") (pin "SH3") (pinfunction "SHIELD_SH3") (pintype "passive"))
      (node (ref "J4") (pin "SH4") (pinfunction "SHIELD_SH4") (pintype "passive"))
      (node (ref "R1_USB") (pin "1") (pinfunction "1_1") (pintype "bidirectional"))
      (node (ref "R2_EP_DR") (pin "1") (pinfunction "1_1") (pintype "bidirectional"))
      (node (ref "R2_USB") (pin "2") (pinfunction "2_2") (pintype "bidirectional"))
      (node (ref "R3") (pin "1") (pinfunction "1_1") (pintype "bidirectional"))
      (node (ref "R9") (pin "1") (pinfunction "1_1") (pintype "bidirectional"))
      (node (ref "R_TYPE_SEL") (pin "1") (pinfunction "1_1") (pintype "bidirectional"))
      (node (ref "SJ1") (pin "1") (pinfunction "1_1") (pintype "passive"))
      (node (ref "SW_DN") (pin "1") (pinfunction "1_1") (pintype "passive"))
      (node (ref "SW_ENT") (pin "1") (pinfunction "1_1") (pintype "passive"))
      (node (ref "SW_UP") (pin "1") (pinfunction "1_1") (pintype "passive"))
      (node (ref "TP_BAT_GND") (pin "TP") (pinfunction "TP_TP") (pintype "input"))
      (node (ref "TP_GND") (pin "TP") (pinfunction "TP_TP") (pintype "input"))
      (node (ref "U2") (pin "P$74") (pinfunction "VSS_PAD_P$74") (pintype "bidirectional"))
      (node (ref "U2") (pin "P$75") (pinfunction "VSS_PAD_P$75") (pintype "bidirectional"))
      (node (ref "U2") (pin "P$76") (pinfunction "VSS_PAD_P$76") (pintype "bidirectional"))
      (node (ref "U2") (pin "P$77") (pinfunction "VSS_PAD_P$77") (pintype "bidirectional"))
      (node (ref "U2") (pin "P$78") (pinfunction "VSS_PAD_P$78") (pintype "bidirectional"))
      (node (ref "U2") (pin "P$79") (pinfunction "VSS_PAD_P$79") (pintype "bidirectional"))
      (node (ref "U2") (pin "P$80") (pinfunction "VSS_PAD_P$80") (pintype "bidirectional"))
      (node (ref "U2") (pin "P$81") (pinfunction "VSS_PAD_P$81") (pintype "bidirectional"))
      (node (ref "U2") (pin "P$82") (pinfunction "VSS_PAD_P$82") (pintype "bidirectional"))
      (node (ref "U2") (pin "P$83") (pinfunction "VSS_PAD_P$83") (pintype "bidirectional"))
      (node (ref "U2") (pin "P$84") (pinfunction "VSS_PAD_P$84") (pintype "bidirectional"))
      (node (ref "U2") (pin "P$85") (pinfunction "VSS_PAD_P$85") (pintype "bidirectional"))
      (node (ref "U2") (pin "P$86") (pinfunction "VSS_PAD_P$86") (pintype "bidirectional"))
      (node (ref "U2") (pin "P$87") (pinfunction "VSS_PAD_P$87") (pintype "bidirectional"))
      (node (ref "U2") (pin "P$88") (pinfunction "VSS_PAD_P$88") (pintype "bidirectional"))
      (node (ref "U2") (pin "P$89") (pinfunction "VSS_PAD_P$89") (pintype "bidirectional"))
      (node (ref "U2") (pin "P$90") (pinfunction "VSS_PAD_P$90") (pintype "bidirectional"))
      (node (ref "U2") (pin "P$B7") (pinfunction "VSS_P$B7") (pintype "power_in"))
      (node (ref "U2") (pin "P$F23") (pinfunction "VSS_PA_P$F23") (pintype "bidirectional"))
      (node (ref "U3") (pin "1") (pinfunction "CTG_1") (pintype "power_in"))
      (node (ref "U3") (pin "4") (pinfunction "GND_4") (pintype "power_in"))
      (node (ref "U3") (pin "6") (pinfunction "QSTRT_6") (pintype "input"))
      (node (ref "U3") (pin "9") (pinfunction "EP_9") (pintype "power_in"))
      (node (ref "X1") (pin "2") (pinfunction "2_2") (pintype "passive"))
      (node (ref "X1") (pin "4") (pinfunction "4_4") (pintype "passive"))
    )
    (net (code "16") (name "HAPTIC_EN") (class "Default")
      (node (ref "IC4") (pin "A1") (pinfunction "EN_A1") (pintype "bidirectional"))
      (node (ref "U2") (pin "P$U1") (pinfunction "P0.12_P$U1") (pintype "bidirectional"))
    )
    (net (code "17") (name "IMU_INT1") (class "Default")
      (node (ref "IC3") (pin "5") (pinfunction "INT1_5") (pintype "bidirectional"))
      (node (ref "U2") (pin "P$N1") (pinfunction "P0.08_P$N1") (pintype "bidirectional"))
    )
    (net (code "18") (name "IMU_INT2") (class "Default")
      (node (ref "IC3") (pin "6") (pinfunction "INT2_6") (pintype "bidirectional"))
      (node (ref "U2") (pin "P$P2") (pinfunction "P1.08_P$P2") (pintype "bidirectional"))
    )
    (net (code "19") (name "LX1") (class "Default")
      (node (ref "IC2") (pin "B2") (pinfunction "SW1_1_B2") (pintype "bidirectional"))
      (node (ref "IC2") (pin "B3") (pinfunction "SW1_2_B3") (pintype "bidirectional"))
      (node (ref "L7") (pin "1") (pinfunction "1_1") (pintype "bidirectional"))
    )
    (net (code "20") (name "LX2") (class "Default")
      (node (ref "IC2") (pin "D2") (pinfunction "SW2_1_D2") (pintype "bidirectional"))
      (node (ref "IC2") (pin "D3") (pinfunction "SW2_2_D3") (pintype "bidirectional"))
      (node (ref "L7") (pin "2") (pinfunction "2_2") (pintype "bidirectional"))
    )
    (net (code "21") (name "MOSI") (class "Default")
      (node (ref "J2") (pin "14") (pinfunction "14_14") (pintype "bidirectional"))
      (node (ref "U2") (pin "P$B13") (pinfunction "P0.03/AIN1_P$B13") (pintype "bidirectional"))
    )
    (net (code "22") (name "N$3") (class "Default")
      (node (ref "IC3") (pin "2") (pinfunction "SDX_2") (pintype "bidirectional"))
    )
    (net (code "23") (name "N$6") (class "Default")
      (node (ref "IC3") (pin "3") (pinfunction "VDDIO_3") (pintype "bidirectional"))
    )
    (net (code "24") (name "Net-(ANT1-FEED)") (class "Default")
      (node (ref "ANT1") (pin "1") (pinfunction "FEED_1") (pintype "input"))
      (node (ref "C22") (pin "1") (pinfunction "1_1") (pintype "passive"))
      (node (ref "C4") (pin "1") (pinfunction "1_1") (pintype "passive"))
      (node (ref "L1") (pin "2") (pinfunction "2_2") (pintype "passive"))
    )
    (net (code "25") (name "Net-(D2-A)") (class "Default")
      (node (ref "C2-EP-DR1") (pin "1") (pinfunction "1_1") (pintype "passive"))
      (node (ref "D2") (pin "2") (pinfunction "A_2") (pintype "bidirectional"))
      (node (ref "D4") (pin "1") (pinfunction "K_1") (pintype "bidirectional"))
    )
    (net (code "26") (name "Net-(D5-A)") (class "Default")
      (node (ref "C2-EP-DR1") (pin "2") (pinfunction "2_2") (pintype "passive"))
      (node (ref "D5") (pin "2") (pinfunction "A_2") (pintype "bidirectional"))
      (node (ref "L5") (pin "1") (pinfunction "1_1") (pintype "passive"))
      (node (ref "Q3") (pin "3") (pinfunction "D_3") (pintype "bidirectional"))
    )
    (net (code "27") (name "Net-(EPD_C1-Pad2)") (class "Default")
      (node (ref "EPD_C1") (pin "2") (pinfunction "2_2") (pintype "passive"))
      (node (ref "J2") (pin "5") (pinfunction "5_5") (pintype "bidirectional"))
    )
    (net (code "28") (name "Net-(EPD_C2-Pad2)") (class "Default")
      (node (ref "EPD_C2") (pin "2") (pinfunction "2_2") (pintype "passive"))
      (node (ref "J2") (pin "4") (pinfunction "4_4") (pintype "bidirectional"))
    )
    (net (code "29") (name "Net-(EPD_C6-Pad2)") (class "Default")
      (node (ref "EPD_C6") (pin "2") (pinfunction "2_2") (pintype "passive"))
      (node (ref "J2") (pin "18") (pinfunction "18_18") (pintype "bidirectional"))
    )
    (net (code "30") (name "Net-(EPD_C7-Pad2)") (class "Default")
      (node (ref "EPD_C7") (pin "2") (pinfunction "2_2") (pintype "passive"))
      (node (ref "J2") (pin "19") (pinfunction "19_19") (pintype "bidirectional"))
    )
    (net (code "31") (name "Net-(EPD_C8-Pad2)") (class "Default")
      (node (ref "EPD_C8") (pin "2") (pinfunction "2_2") (pintype "passive"))
      (node (ref "J2") (pin "20") (pinfunction "20_20") (pintype "bidirectional"))
    )
    (net (code "32") (name "Net-(EPD_C11-Pad2)") (class "Default")
      (node (ref "EPD_C11") (pin "2") (pinfunction "2_2") (pintype "passive"))
      (node (ref "J2") (pin "23") (pinfunction "23_23") (pintype "bidirectional"))
    )
    (net (code "33") (name "Net-(EPD_C12-Pad2)") (class "Default")
      (node (ref "EPD_C12") (pin "2") (pinfunction "2_2") (pintype "passive"))
      (node (ref "J2") (pin "24") (pinfunction "24_24") (pintype "bidirectional"))
    )
    (net (code "34") (name "Net-(IC1-TS{slash}MR)") (class "Default")
      (node (ref "IC1") (pin "D1") (pinfunction "TS/MR_D1") (pintype "bidirectional"))
      (node (ref "R9") (pin "2") (pinfunction "2_2") (pintype "bidirectional"))
    )
    (net (code "35") (name "Net-(IC2-SCL)") (class "Default")
      (node (ref "IC2") (pin "D1") (pinfunction "SCL_D1") (pintype "bidirectional"))
      (node (ref "R4") (pin "1") (pinfunction "1_1") (pintype "bidirectional"))
    )
    (net (code "36") (name "Net-(IC2-SDA)") (class "Default")
      (node (ref "IC2") (pin "E1") (pinfunction "SDA_E1") (pintype "bidirectional"))
      (node (ref "R2") (pin "1") (pinfunction "1_1") (pintype "bidirectional"))
    )
    (net (code "37") (name "Net-(IC3-SDO)") (class "Default")
      (node (ref "IC3") (pin "1") (pinfunction "SDO_1") (pintype "bidirectional"))
      (node (ref "R3") (pin "2") (pinfunction "2_2") (pintype "bidirectional"))
    )
    (net (code "38") (name "Net-(IC4-REG)") (class "Default")
      (node (ref "C32") (pin "2") (pinfunction "2_2") (pintype "passive"))
      (node (ref "IC4") (pin "A2") (pinfunction "REG_A2") (pintype "bidirectional"))
    )
    (net (code "39") (name "Net-(J4-CC1)") (class "Default")
      (node (ref "J4") (pin "A5") (pinfunction "CC1_A5") (pintype "bidirectional"))
      (node (ref "R1_USB") (pin "2") (pinfunction "2_2") (pintype "bidirectional"))
    )
    (net (code "40") (name "Net-(J4-CC2)") (class "Default")
      (node (ref "J4") (pin "B5") (pinfunction "CC2_B5") (pintype "bidirectional"))
      (node (ref "R2_USB") (pin "1") (pinfunction "1_1") (pintype "bidirectional"))
    )
    (net (code "41") (name "Net-(L2-Pad1)") (class "Default")
      (node (ref "L2") (pin "1") (pinfunction "1_1") (pintype "passive"))
      (node (ref "L3") (pin "2") (pinfunction "2_2") (pintype "passive"))
    )
    (net (code "42") (name "Net-(R1_EP_DR-Pad1)") (class "Default")
      (node (ref "R1_EP_DR") (pin "1") (pinfunction "1_1") (pintype "bidirectional"))
      (node (ref "R_TYPE_SEL") (pin "2") (pinfunction "2_2") (pintype "bidirectional"))
      (node (ref "SJ1") (pin "2") (pinfunction "2_2") (pintype "passive"))
    )
    (net (code "43") (name "Net-(U2-ANT)") (class "Default")
      (node (ref "C3") (pin "1") (pinfunction "1_1") (pintype "passive"))
      (node (ref "L1") (pin "1") (pinfunction "1_1") (pintype "passive"))
      (node (ref "U2") (pin "P$H23") (pinfunction "ANT_P$H23") (pintype "bidirectional"))
    )
    (net (code "44") (name "Net-(U2-DCC)") (class "Default")
      (node (ref "L2") (pin "2") (pinfunction "2_2") (pintype "passive"))
      (node (ref "U2") (pin "P$B3") (pinfunction "DCC_P$B3") (pintype "output"))
    )
    (net (code "45") (name "Net-(U2-DEC1)") (class "Default")
      (node (ref "C5") (pin "1") (pinfunction "1_1") (pintype "passive"))
      (node (ref "U2") (pin "P$C1") (pinfunction "DEC1_P$C1") (pintype "power_in"))
    )
    (net (code "46") (name "Net-(U2-DEC2)") (class "Default")
      (node (ref "C13") (pin "2") (pinfunction "2_2") (pintype "passive"))
      (node (ref "U2") (pin "P$A18") (pinfunction "DEC2_P$A18") (pintype "bidirectional"))
    )
    (net (code "47") (name "Net-(U2-DEC3V3)") (class "Default")
      (node (ref "C20") (pin "1") (pinfunction "1_1") (pintype "passive"))
      (node (ref "U2") (pin "P$AC5") (pinfunction "DEC3V3_P$AC5") (pintype "bidirectional"))
    )
    (net (code "48") (name "Net-(U2-DEC5)") (class "Default")
      (node (ref "C9") (pin "1") (pinfunction "1_1") (pintype "passive"))
      (node (ref "U2") (pin "P$N24") (pinfunction "DEC5_P$N24") (pintype "bidirectional"))
    )
    (net (code "49") (name "Net-(U2-XC1)") (class "Default")
      (node (ref "C1") (pin "1") (pinfunction "1_1") (pintype "passive"))
      (node (ref "U2") (pin "P$B24") (pinfunction "XC1_P$B24") (pintype "input"))
      (node (ref "X1") (pin "1") (pinfunction "1_1") (pintype "passive"))
    )
    (net (code "50") (name "Net-(U2-XC2)") (class "Default")
      (node (ref "C2") (pin "1") (pinfunction "1_1") (pintype "passive"))
      (node (ref "U2") (pin "P$A23") (pinfunction "XC2_P$A23") (pintype "output"))
      (node (ref "X1") (pin "3") (pinfunction "3_3") (pintype "passive"))
    )
    (net (code "51") (name "OUT+") (class "Default")
      (node (ref "IC4") (pin "A3") (pinfunction "OUT+_A3") (pintype "bidirectional"))
      (node (ref "TP_OP") (pin "TP") (pinfunction "TP_TP") (pintype "input"))
    )
    (net (code "52") (name "OUT-") (class "Default")
      (node (ref "IC4") (pin "C3") (pinfunction "OUT-_C3") (pintype "bidirectional"))
      (node (ref "TP_ON") (pin "TP") (pinfunction "TP_TP") (pintype "input"))
    )
    (net (code "53") (name "P0.00{slash}XL1") (class "Default")
      (node (ref "C17") (pin "2") (pinfunction "2_2") (pintype "passive"))
      (node (ref "U2") (pin "P$D2") (pinfunction "P0.00/XL1_P$D2") (pintype "bidirectional"))
      (node (ref "X2") (pin "2") (pinfunction "2_2") (pintype "passive"))
    )
    (net (code "54") (name "P0.00{slash}XL2") (class "Default")
      (node (ref "C18") (pin "2") (pinfunction "2_2") (pintype "passive"))
      (node (ref "U2") (pin "P$F2") (pinfunction "P0.01/XL2_P$F2") (pintype "bidirectional"))
      (node (ref "X2") (pin "1") (pinfunction "1_1") (pintype "passive"))
    )
    (net (code "55") (name "P0.04") (class "Default")
      (node (ref "U2") (pin "P$J1") (pinfunction "P0.04/AIN2_P$J1") (pintype "bidirectional"))
    )
    (net (code "56") (name "P0.09") (class "Default")
      (node (ref "U2") (pin "P$L24") (pinfunction "P0.09/NFC1_P$L24") (pintype "bidirectional"))
    )
    (net (code "57") (name "P0.13") (class "Default")
      (node (ref "C30") (pin "1") (pinfunction "1_1") (pintype "passive"))
      (node (ref "R5") (pin "1") (pinfunction "1_1") (pintype "bidirectional"))
      (node (ref "SW_UP") (pin "2") (pinfunction "2_2") (pintype "passive"))
      (node (ref "U2") (pin "P$AD8") (pinfunction "P0.13_P$AD8") (pintype "bidirectional"))
    )
    (net (code "58") (name "P0.14") (class "Default")
      (node (ref "C31") (pin "1") (pinfunction "1_1") (pintype "passive"))
      (node (ref "R8") (pin "1") (pinfunction "1_1") (pintype "bidirectional"))
      (node (ref "SW_ENT") (pin "2") (pinfunction "2_2") (pintype "passive"))
      (node (ref "U2") (pin "P$AC9") (pinfunction "P0.14_P$AC9") (pintype "bidirectional"))
    )
    (net (code "59") (name "P0.19") (class "Default")
      (node (ref "U2") (pin "P$AC15") (pinfunction "P0.19_P$AC15") (pintype "bidirectional"))
    )
    (net (code "60") (name "P0.20") (class "Default")
      (node (ref "U2") (pin "P$AD16") (pinfunction "P0.20_P$AD16") (pintype "bidirectional"))
    )
    (net (code "61") (name "P0.21") (class "Default")
      (node (ref "U2") (pin "P$AC17") (pinfunction "P0.21_P$AC17") (pintype "bidirectional"))
    )
    (net (code "62") (name "P0.22") (class "Default")
      (node (ref "U2") (pin "P$AD18") (pinfunction "P0.22_P$AD18") (pintype "bidirectional"))
    )
    (net (code "63") (name "P0.23") (class "Default")
      (node (ref "U2") (pin "P$AC19") (pinfunction "P0.23_P$AC19") (pintype "bidirectional"))
    )
    (net (code "64") (name "P0.24") (class "Default")
      (node (ref "U2") (pin "P$AD20") (pinfunction "P0.24_P$AD20") (pintype "bidirectional"))
    )
    (net (code "65") (name "P0.25") (class "Default")
      (node (ref "U2") (pin "P$AC21") (pinfunction "P0.25_P$AC21") (pintype "bidirectional"))
    )
    (net (code "66") (name "P0.26") (class "Default")
      (node (ref "U2") (pin "P$G1") (pinfunction "P0.26_P$G1") (pintype "bidirectional"))
    )
    (net (code "67") (name "P0.27") (class "Default")
      (node (ref "U2") (pin "P$H2") (pinfunction "P0.27_P$H2") (pintype "bidirectional"))
    )
    (net (code "68") (name "P0.28") (class "Default")
      (node (ref "U2") (pin "P$B11") (pinfunction "P0.28/AIN4_P$B11") (pintype "bidirectional"))
    )
    (net (code "69") (name "P0.29") (class "Default")
      (node (ref "U2") (pin "P$A10") (pinfunction "P0.29/AIN5_P$A10") (pintype "bidirectional"))
    )
    (net (code "70") (name "P0.30") (class "Default")
      (node (ref "U2") (pin "P$B9") (pinfunction "P0.30/AIN6_P$B9") (pintype "bidirectional"))
    )
    (net (code "71") (name "P0.31") (class "Default")
      (node (ref "U2") (pin "P$A8") (pinfunction "P0.31/AIN7_P$A8") (pintype "bidirectional"))
    )
    (net (code "72") (name "P1.01") (class "Default")
      (node (ref "Q1") (pin "1") (pinfunction "G_1") (pintype "bidirectional"))
      (node (ref "R_PWR_EPD") (pin "1") (pinfunction "1_1") (pintype "bidirectional"))
      (node (ref "U2") (pin "P$Y23") (pinfunction "P1.01_P$Y23") (pintype "bidirectional"))
    )
    (net (code "73") (name "P1.02") (class "Default")
      (node (ref "C29") (pin "1") (pinfunction "1_1") (pintype "passive"))
      (node (ref "R7") (pin "1") (pinfunction "1_1") (pintype "bidirectional"))
      (node (ref "SW_DN") (pin "2") (pinfunction "2_2") (pintype "passive"))
      (node (ref "U2") (pin "P$W24") (pinfunction "P1.02_P$W24") (pintype "bidirectional"))
    )
    (net (code "74") (name "P1.03") (class "Default")
      (node (ref "U2") (pin "P$V23") (pinfunction "P1.03_P$V23") (pintype "bidirectional"))
    )
    (net (code "75") (name "P1.04") (class "Default")
      (node (ref "U2") (pin "P$U24") (pinfunction "P1.04_P$U24") (pintype "bidirectional"))
    )
    (net (code "76") (name "P1.05") (class "Default")
      (node (ref "U2") (pin "P$T23") (pinfunction "P1.05_P$T23") (pintype "bidirectional"))
    )
    (net (code "77") (name "P1.06") (class "Default")
      (node (ref "U2") (pin "P$R24") (pinfunction "P1.06_P$R24") (pintype "bidirectional"))
    )
    (net (code "78") (name "P1.07") (class "Default")
      (node (ref "U2") (pin "P$P23") (pinfunction "P1.07_P$P23") (pintype "bidirectional"))
    )
    (net (code "79") (name "P1.09") (class "Default")
      (node (ref "U2") (pin "P$R1") (pinfunction "P1.09_P$R1") (pintype "bidirectional"))
    )
    (net (code "80") (name "P1.10") (class "Default")
      (node (ref "U2") (pin "P$A20") (pinfunction "P1.10_P$A20") (pintype "bidirectional"))
    )
    (net (code "81") (name "P1.11") (class "Default")
      (node (ref "U2") (pin "P$B19") (pinfunction "P1.11_P$B19") (pintype "bidirectional"))
    )
    (net (code "82") (name "P1.12") (class "Default")
      (node (ref "U2") (pin "P$B17") (pinfunction "P1.12_P$B17") (pintype "bidirectional"))
    )
    (net (code "83") (name "P1.13") (class "Default")
      (node (ref "U2") (pin "P$A16") (pinfunction "P1.13_P$A16") (pintype "bidirectional"))
    )
    (net (code "84") (name "P1.14") (class "Default")
      (node (ref "U2") (pin "P$B15") (pinfunction "P1.14_P$B15") (pintype "bidirectional"))
    )
    (net (code "85") (name "P1.15") (class "Default")
      (node (ref "U2") (pin "P$A14") (pinfunction "P1.15_P$A14") (pintype "bidirectional"))
    )
    (net (code "86") (name "PMIC_INT") (class "Default")
      (node (ref "IC1") (pin "A1") (pinfunction "~{INT}_A1") (pintype "bidirectional"))
      (node (ref "U2") (pin "P$T2") (pinfunction "P0.11_P$T2") (pintype "bidirectional"))
    )
    (net (code "87") (name "PREVGH") (class "Default")
      (node (ref "D5") (pin "1") (pinfunction "K_1") (pintype "bidirectional"))
      (node (ref "EPD_C9") (pin "2") (pinfunction "2_2") (pintype "passive"))
      (node (ref "J2") (pin "21") (pinfunction "21_21") (pintype "bidirectional"))
    )
    (net (code "88") (name "PREVGL") (class "Default")
      (node (ref "D4") (pin "2") (pinfunction "A_2") (pintype "bidirectional"))
      (node (ref "EPD_C10") (pin "2") (pinfunction "2_2") (pintype "passive"))
      (node (ref "J2") (pin "22") (pinfunction "22_22") (pintype "bidirectional"))
    )
    (net (code "89") (name "RESE") (class "Default")
      (node (ref "J2") (pin "3") (pinfunction "3_3") (pintype "bidirectional"))
      (node (ref "Q3") (pin "2") (pinfunction "S_2") (pintype "bidirectional"))
      (node (ref "R1_EP_DR") (pin "2") (pinfunction "2_2") (pintype "bidirectional"))
    )
    (net (code "90") (name "RESET") (class "Default")
      (node (ref "J1") (pin "6") (pinfunction "6_6") (pintype "bidirectional"))
      (node (ref "TP_RESET") (pin "TP") (pinfunction "TP_TP") (pintype "input"))
      (node (ref "U2") (pin "P$AC13") (pinfunction "P0.18/RESET_P$AC13") (pintype "bidirectional"))
    )
    (net (code "91") (name "SCK") (class "Default")
      (node (ref "J2") (pin "13") (pinfunction "13_13") (pintype "bidirectional"))
      (node (ref "U2") (pin "P$A12") (pinfunction "P0.02/AIN0_P$A12") (pintype "bidirectional"))
    )
    (net (code "92") (name "SCL") (class "Default")
      (node (ref "IC1") (pin "B1") (pinfunction "SCL_B1") (pintype "bidirectional"))
      (node (ref "IC3") (pin "12") (pinfunction "SCX_12") (pintype "bidirectional"))
      (node (ref "IC4") (pin "C1") (pinfunction "SCL_C1") (pintype "bidirectional"))
      (node (ref "R17") (pin "2") (pinfunction "2_2") (pintype "bidirectional"))
      (node (ref "R4") (pin "2") (pinfunction "2_2") (pintype "bidirectional"))
      (node (ref "TP_SCL") (pin "TP") (pinfunction "TP_TP") (pintype "input"))
      (node (ref "U2") (pin "P$M2") (pinfunction "P0.07_P$M2") (pintype "bidirectional"))
      (node (ref "U3") (pin "7") (pinfunction "SCL_7") (pintype "input"))
    )
    (net (code "93") (name "SDA") (class "Default")
      (node (ref "IC1") (pin "C1") (pinfunction "SDA_C1") (pintype "bidirectional"))
      (node (ref "IC4") (pin "B2") (pinfunction "SDA_B2") (pintype "bidirectional"))
      (node (ref "R18") (pin "2") (pinfunction "2_2") (pintype "bidirectional"))
      (node (ref "R2") (pin "2") (pinfunction "2_2") (pintype "bidirectional"))
      (node (ref "TP_SDA") (pin "TP") (pinfunction "TP_TP") (pintype "input"))
      (node (ref "U2") (pin "P$L1") (pinfunction "P0.06_P$L1") (pintype "bidirectional"))
      (node (ref "U3") (pin "8") (pinfunction "SDA_8") (pintype "bidirectional"))
    )
    (net (code "94") (name "SWDCLK") (class "Default")
      (node (ref "J1") (pin "4") (pinfunction "4_4") (pintype "bidirectional"))
      (node (ref "TP_SWDCLK") (pin "TP") (pinfunction "TP_TP") (pintype "input"))
      (node (ref "U2") (pin "P$AA24") (pinfunction "SWDCLK_P$AA24") (pintype "input"))
    )
    (net (code "95") (name "SWDIO") (class "Default")
      (node (ref "J1") (pin "2") (pinfunction "2_2") (pintype "bidirectional"))
      (node (ref "TP_SWDIO") (pin "TP") (pinfunction "TP_TP") (pintype "input"))
      (node (ref "U2") (pin "P$AC24") (pinfunction "SWDIO_P$AC24") (pintype "bidirectional"))
    )
    (net (code "96") (name "SWO") (class "Default")
      (node (ref "TP_SWO") (pin "TP") (pinfunction "TP_TP") (pintype "input"))
      (node (ref "U2") (pin "P$AD22") (pinfunction "P1.00_P$AD22") (pintype "bidirectional"))
    )
    (net (code "97") (name "VBAT") (class "Default")
      (node (ref "C27") (pin "1") (pinfunction "1_1") (pintype "passive"))
      (node (ref "C37") (pin "1") (pinfunction "1_1") (pintype "passive"))
      (node (ref "IC1") (pin "C2") (pinfunction "BAT_C2") (pintype "bidirectional"))
      (node (ref "TP_VBAT") (pin "TP") (pinfunction "TP_TP") (pintype "input"))
      (node (ref "U3") (pin "2") (pinfunction "CELL_2") (pintype "power_in"))
      (node (ref "U3") (pin "3") (pinfunction "VDD_3") (pintype "power_in"))
    )
    (net (code "98") (name "VBUS") (class "Default")
      (node (ref "C21") (pin "1") (pinfunction "1_1") (pintype "passive"))
      (node (ref "C38") (pin "2") (pinfunction "2_2") (pintype "passive"))
      (node (ref "C42") (pin "1") (pinfunction "1_1") (pintype "passive"))
      (node (ref "C43") (pin "1") (pinfunction "1_1") (pintype "passive"))
      (node (ref "D3") (pin "5") (pinfunction "VBUS_5") (pintype "bidirectional"))
      (node (ref "IC1") (pin "A2") (pinfunction "IN_A2") (pintype "bidirectional"))
      (node (ref "J4") (pin "A4_B9") (pinfunction "VBUS_A4_B9") (pintype "power_in"))
      (node (ref "J4") (pin "A9_B4") (pinfunction "VBUS_A9_B4") (pintype "power_in"))
      (node (ref "U2") (pin "P$AD2") (pinfunction "VBUS_P$AD2") (pintype "power_in"))
    )
    (net (code "99") (name "VREG") (class "Default")
      (node (ref "C23") (pin "2") (pinfunction "2_2") (pintype "passive"))
      (node (ref "C24") (pin "2") (pinfunction "2_2") (pintype "passive"))
      (node (ref "C39") (pin "2") (pinfunction "2_2") (pintype "passive"))
      (node (ref "IC1") (pin "B2") (pinfunction "SYS_B2") (pintype "bidirectional"))
      (node (ref "IC2") (pin "A1") (pinfunction "EN_A1") (pintype "bidirectional"))
      (node (ref "IC2") (pin "A2") (pinfunction "VIN_1_A2") (pintype "bidirectional"))
      (node (ref "IC2") (pin "A3") (pinfunction "VIN_2_A3") (pintype "bidirectional"))
      (node (ref "TP_VREG") (pin "TP") (pinfunction "TP_TP") (pintype "input"))
    )
    (net (code "100") (name "unconnected-(ANT1-NC-Pad2)") (class "Default")
      (node (ref "ANT1") (pin "2") (pinfunction "NC_2") (pintype "no_connect"))
    )
    (net (code "101") (name "unconnected-(IC3-ASCL-Pad11)") (class "Default")
      (node (ref "IC3") (pin "11") (pinfunction "ASCL_11") (pintype "bidirectional"))
    )
    (net (code "102") (name "unconnected-(IC3-ASDA-Pad4)") (class "Default")
      (node (ref "IC3") (pin "4") (pinfunction "ASDA_4") (pintype "bidirectional"))
    )
    (net (code "103") (name "unconnected-(J2-Pad1)") (class "Default")
      (node (ref "J2") (pin "1") (pinfunction "1_1") (pintype "bidirectional"))
    )
    (net (code "104") (name "unconnected-(J2-Pad6)") (class "Default")
      (node (ref "J2") (pin "6") (pinfunction "6_6") (pintype "bidirectional"))
    )
    (net (code "105") (name "unconnected-(J2-Pad7)") (class "Default")
      (node (ref "J2") (pin "7") (pinfunction "7_7") (pintype "bidirectional"))
    )
    (net (code "106") (name "unconnected-(J4-SBU1-PadA8)") (class "Default")
      (node (ref "J4") (pin "A8") (pinfunction "SBU1_A8") (pintype "bidirectional"))
    )
    (net (code "107") (name "unconnected-(J4-SBU2-PadB8)") (class "Default")
      (node (ref "J4") (pin "B8") (pinfunction "SBU2_B8") (pintype "bidirectional"))
    )
    (net (code "108") (name "unconnected-(U2-DCCH-PadP$AB2)") (class "Default")
      (node (ref "U2") (pin "P$AB2") (pinfunction "DCCH_P$AB2") (pintype "bidirectional"))
    )
  )
)
